# SBC_TMS9918A_ISA.net
KiCad netlist of a schematic drawn in EAGLE
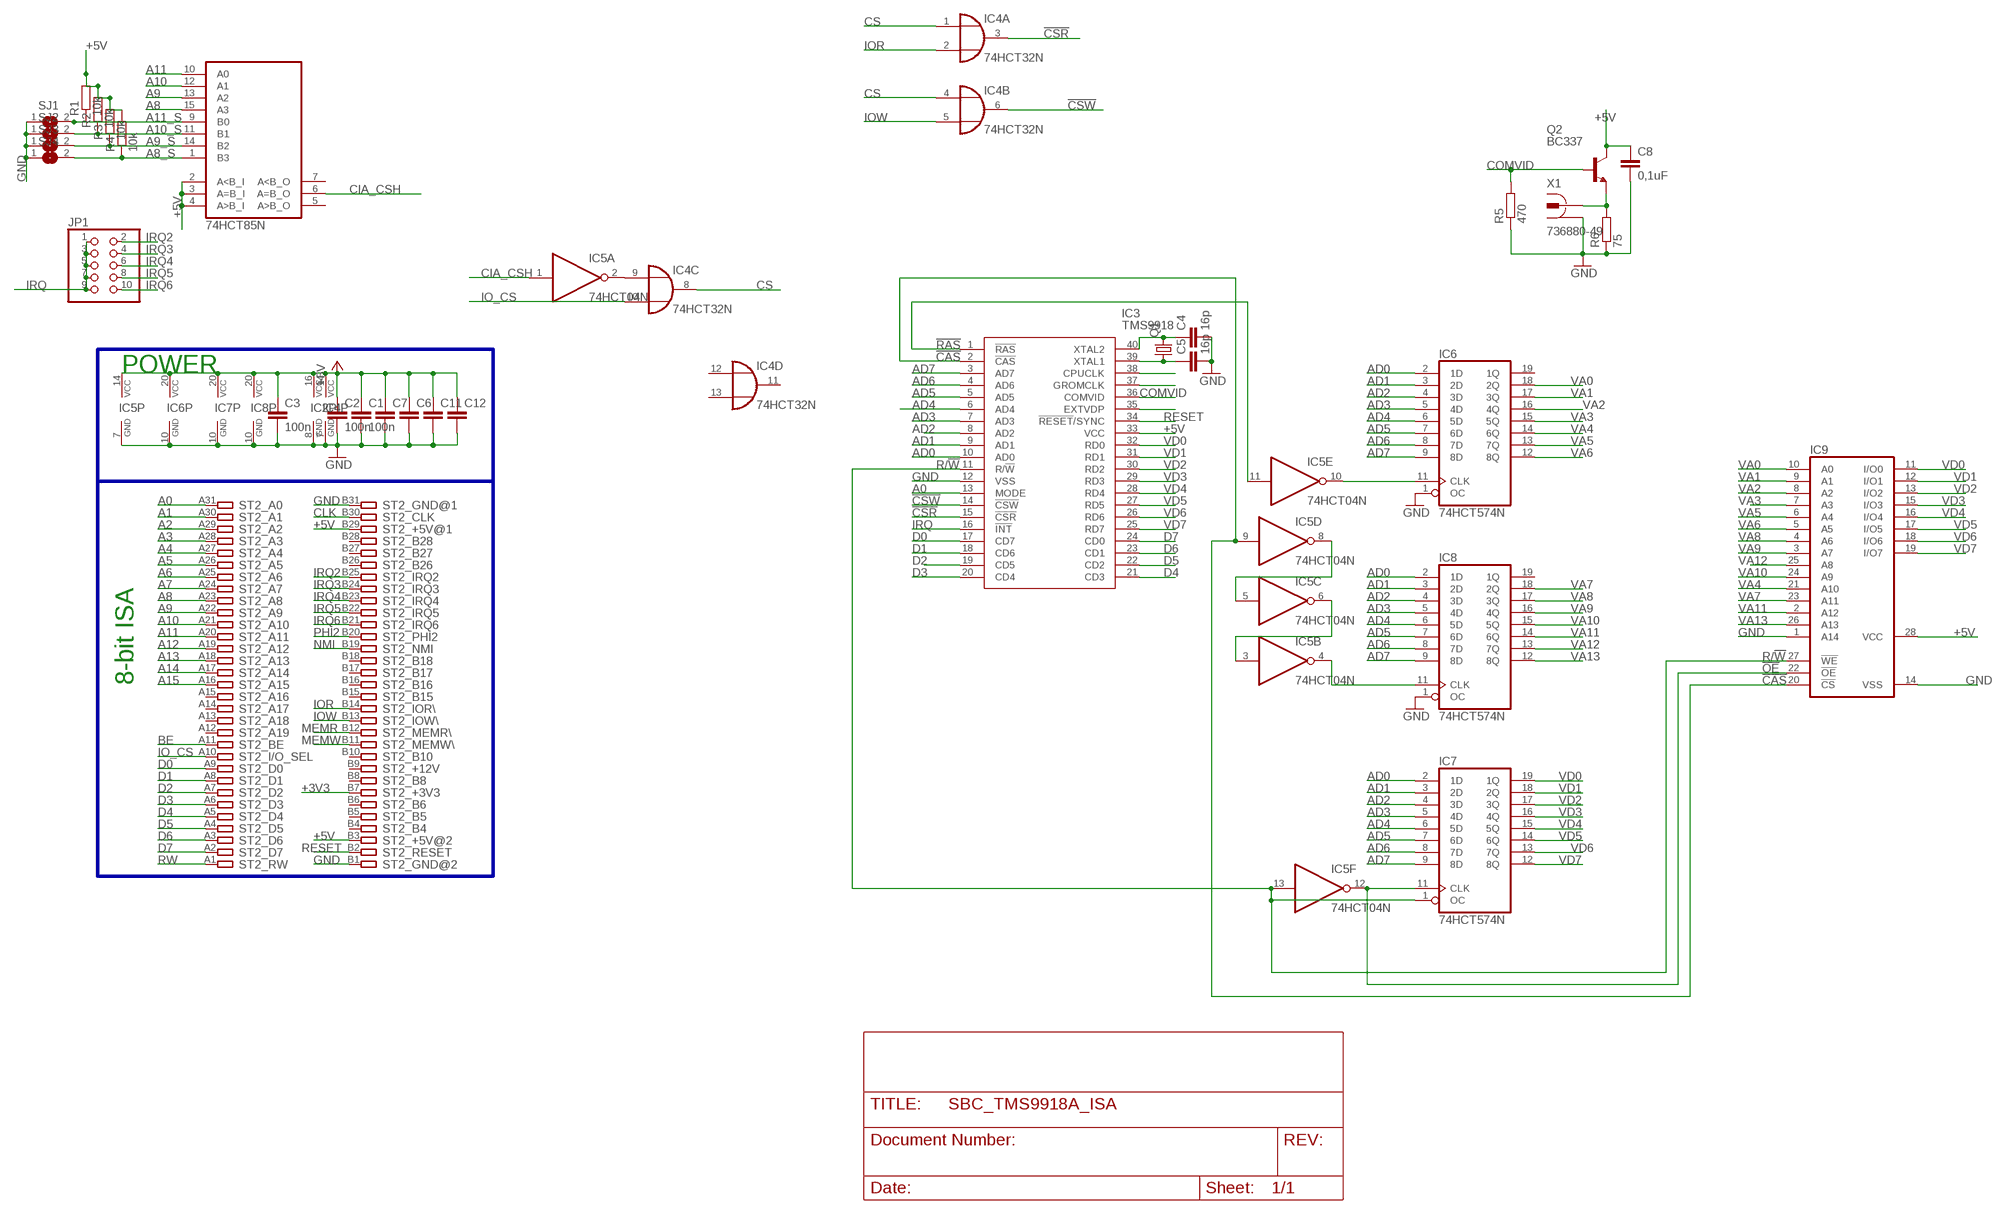
[diagram p0: schematic, sheet 1]

(export (version "E")
  (design (tool "Eeschema 10.0.6"))
  (components
    (comp (ref "C1")
      (value "100n")
      (footprint "eagle-import:C050-025X075")
      (libsource (lib "eagle-import") (part "C-EU050-025X075"))
    )
    (comp (ref "C2")
      (value "100n")
      (footprint "eagle-import:C050-025X075")
      (libsource (lib "eagle-import") (part "C-EU050-025X075"))
    )
    (comp (ref "C3")
      (value "100n")
      (footprint "eagle-import:C050-025X075")
      (libsource (lib "eagle-import") (part "C-EU050-025X075"))
    )
    (comp (ref "C4")
      (value "16p")
      (footprint "eagle-import:C050-024X044")
      (libsource (lib "eagle-import") (part "rcl_334_C-EU050-024X044"))
    )
    (comp (ref "C5")
      (value "16p")
      (footprint "eagle-import:C050-024X044")
      (libsource (lib "eagle-import") (part "rcl_334_C-EU050-024X044"))
    )
    (comp (ref "C6")
      (value "C-EU050-035X075")
      (footprint "eagle-import:C050-035X075")
      (libsource (lib "eagle-import") (part "rcl_334_C-EU050-035X075"))
    )
    (comp (ref "C7")
      (value "C-EU050-035X075")
      (footprint "eagle-import:C050-035X075")
      (libsource (lib "eagle-import") (part "rcl_334_C-EU050-035X075"))
    )
    (comp (ref "C8")
      (value "0,1uF")
      (footprint "eagle-import:C050-024X044")
      (libsource (lib "eagle-import") (part "rcl_334_C-EU050-024X044"))
    )
    (comp (ref "C11")
      (value "C-EU050-035X075")
      (footprint "eagle-import:C050-035X075")
      (libsource (lib "eagle-import") (part "rcl_334_C-EU050-035X075"))
    )
    (comp (ref "C12")
      (value "C-EU050-035X075")
      (footprint "eagle-import:C050-035X075")
      (libsource (lib "eagle-import") (part "rcl_334_C-EU050-035X075"))
    )
    (comp (ref "IC2")
      (value "74HCT85N")
      (footprint "eagle-import:DIL16")
      (libsource (lib "eagle-import") (part "7485NHCT"))
    )
    (comp (ref "IC3")
      (value "TMS9918")
      (footprint "eagle-import:DIP1524W53P254L5310H508Q40N")
      (libsource (lib "eagle-import") (part "TMS9918"))
    )
    (comp (ref "IC4")
      (value "74HCT32N")
      (footprint "eagle-import:DIL14")
      (libsource (lib "eagle-import") (part "7432NHCT"))
    )
    (comp (ref "IC5")
      (value "74HCT04N")
      (footprint "eagle-import:DIL14")
      (libsource (lib "eagle-import") (part "7404NHCT"))
    )
    (comp (ref "IC6")
      (value "74HCT574N")
      (footprint "eagle-import:DIL20")
      (libsource (lib "eagle-import") (part "74574NHCT"))
    )
    (comp (ref "IC7")
      (value "74HCT574N")
      (footprint "eagle-import:DIL20")
      (libsource (lib "eagle-import") (part "74574NHCT"))
    )
    (comp (ref "IC8")
      (value "74HCT574N")
      (footprint "eagle-import:DIL20")
      (libsource (lib "eagle-import") (part "74574NHCT"))
    )
    (comp (ref "IC9")
      (value "62256P")
      (footprint "eagle-import:DIL28-6")
      (libsource (lib "eagle-import") (part "62256P"))
    )
    (comp (ref "JP1")
      (value "PINHD-2X5")
      (footprint "eagle-import:2X05")
      (libsource (lib "eagle-import") (part "PINHD-2X5"))
    )
    (comp (ref "Q1")
      (value "CRYSTALHC49S")
      (footprint "eagle-import:HC49_S")
      (libsource (lib "eagle-import") (part "CRYSTALHC49S"))
    )
    (comp (ref "Q2")
      (value "BC337")
      (footprint "eagle-import:TO92")
      (libsource (lib "eagle-import") (part "BC337"))
    )
    (comp (ref "R1")
      (value "10k")
      (footprint "eagle-import:0207_7")
      (libsource (lib "eagle-import") (part "R-EU_0207/7"))
    )
    (comp (ref "R2")
      (value "10k")
      (footprint "eagle-import:0207_7")
      (libsource (lib "eagle-import") (part "R-EU_0207/7"))
    )
    (comp (ref "R3")
      (value "10k")
      (footprint "eagle-import:0207_7")
      (libsource (lib "eagle-import") (part "R-EU_0207/7"))
    )
    (comp (ref "R4")
      (value "10k")
      (footprint "eagle-import:0207_7")
      (libsource (lib "eagle-import") (part "R-EU_0207/7"))
    )
    (comp (ref "R5")
      (value "470")
      (footprint "eagle-import:0207_7")
      (libsource (lib "eagle-import") (part "R-EU_0207/7"))
    )
    (comp (ref "R6")
      (value "75")
      (footprint "eagle-import:0207_7")
      (libsource (lib "eagle-import") (part "R-EU_0207/7"))
    )
    (comp (ref "SJ1") (value "SJ") (footprint "eagle-import:SJ") (libsource (lib "eagle-import") (part "SJ")))
    (comp (ref "SJ2") (value "SJ") (footprint "eagle-import:SJ") (libsource (lib "eagle-import") (part "SJ")))
    (comp (ref "SJ3") (value "SJ") (footprint "eagle-import:SJ") (libsource (lib "eagle-import") (part "SJ")))
    (comp (ref "SJ4") (value "SJ") (footprint "eagle-import:SJ") (libsource (lib "eagle-import") (part "SJ")))
    (comp (ref "ST2")
      (value "IBM8BIT_ISASHORT")
      (footprint "eagle-import:APP_2X32_SHORT")
      (libsource (lib "eagle-import") (part "IBM8BIT_ISASHORT"))
    )
    (comp (ref "X1")
      (value "736880-49")
      (footprint "eagle-import:736880-49")
      (libsource (lib "eagle-import") (part "736880-49"))
    )
  )
  (nets
    (net (code "1") (name "+5V") (class "Default")
      (node (ref "C1") (pin "1") (pinfunction "1_1") (pintype "passive"))
      (node (ref "C11") (pin "1") (pinfunction "1_1") (pintype "passive"))
      (node (ref "C12") (pin "1") (pinfunction "1_1") (pintype "passive"))
      (node (ref "C2") (pin "1") (pinfunction "1_1") (pintype "passive"))
      (node (ref "C3") (pin "1") (pinfunction "1_1") (pintype "passive"))
      (node (ref "C6") (pin "1") (pinfunction "1_1") (pintype "passive"))
      (node (ref "C7") (pin "1") (pinfunction "1_1") (pintype "passive"))
      (node (ref "C8") (pin "1") (pinfunction "1_1") (pintype "passive"))
      (node (ref "IC2") (pin "16") (pinfunction "VCC_16") (pintype "power_in"))
      (node (ref "IC2") (pin "2") (pinfunction "A<B_I_2") (pintype "input"))
      (node (ref "IC2") (pin "3") (pinfunction "A=B_I_3") (pintype "input"))
      (node (ref "IC2") (pin "4") (pinfunction "A>B_I_4") (pintype "input"))
      (node (ref "IC3") (pin "33") (pinfunction "VCC_33") (pintype "bidirectional"))
      (node (ref "IC4") (pin "14") (pinfunction "VCC_14") (pintype "power_in"))
      (node (ref "IC5") (pin "14") (pinfunction "VCC_14") (pintype "power_in"))
      (node (ref "IC6") (pin "20") (pinfunction "VCC_20") (pintype "power_in"))
      (node (ref "IC7") (pin "20") (pinfunction "VCC_20") (pintype "power_in"))
      (node (ref "IC8") (pin "20") (pinfunction "VCC_20") (pintype "power_in"))
      (node (ref "IC9") (pin "28") (pinfunction "VCC_28") (pintype "power_in"))
      (node (ref "Q2") (pin "3") (pinfunction "C_3") (pintype "passive"))
      (node (ref "R1") (pin "2") (pinfunction "2_2") (pintype "passive"))
      (node (ref "R2") (pin "2") (pinfunction "2_2") (pintype "passive"))
      (node (ref "R3") (pin "2") (pinfunction "2_2") (pintype "passive"))
      (node (ref "R4") (pin "2") (pinfunction "2_2") (pintype "passive"))
      (node (ref "ST2") (pin "B29") (pinfunction "P_B29") (pintype "bidirectional"))
      (node (ref "ST2") (pin "B3") (pinfunction "P_B3") (pintype "bidirectional"))
    )
    (net (code "2") (name "/+3V3") (class "Default")
      (node (ref "ST2") (pin "B7") (pinfunction "P_B7") (pintype "bidirectional"))
    )
    (net (code "3") (name "/A0") (class "Default")
      (node (ref "IC3") (pin "13") (pinfunction "MODE_13") (pintype "bidirectional"))
      (node (ref "ST2") (pin "A31") (pinfunction "P_A31") (pintype "bidirectional"))
    )
    (net (code "4") (name "/A1") (class "Default")
      (node (ref "ST2") (pin "A30") (pinfunction "P_A30") (pintype "bidirectional"))
    )
    (net (code "5") (name "/A2") (class "Default")
      (node (ref "ST2") (pin "A29") (pinfunction "P_A29") (pintype "bidirectional"))
    )
    (net (code "6") (name "/A3") (class "Default")
      (node (ref "ST2") (pin "A28") (pinfunction "P_A28") (pintype "bidirectional"))
    )
    (net (code "7") (name "/A4") (class "Default")
      (node (ref "ST2") (pin "A27") (pinfunction "P_A27") (pintype "bidirectional"))
    )
    (net (code "8") (name "/A5") (class "Default")
      (node (ref "ST2") (pin "A26") (pinfunction "P_A26") (pintype "bidirectional"))
    )
    (net (code "9") (name "/A6") (class "Default")
      (node (ref "ST2") (pin "A25") (pinfunction "P_A25") (pintype "bidirectional"))
    )
    (net (code "10") (name "/A7") (class "Default")
      (node (ref "ST2") (pin "A24") (pinfunction "P_A24") (pintype "bidirectional"))
    )
    (net (code "11") (name "/A8") (class "Default")
      (node (ref "IC2") (pin "15") (pinfunction "A3_15") (pintype "input"))
      (node (ref "ST2") (pin "A23") (pinfunction "P_A23") (pintype "bidirectional"))
    )
    (net (code "12") (name "/A8_S") (class "Default")
      (node (ref "IC2") (pin "1") (pinfunction "B3_1") (pintype "input"))
      (node (ref "R4") (pin "1") (pinfunction "1_1") (pintype "passive"))
      (node (ref "SJ4") (pin "2") (pinfunction "2_2") (pintype "passive"))
    )
    (net (code "13") (name "/A9") (class "Default")
      (node (ref "IC2") (pin "13") (pinfunction "A2_13") (pintype "input"))
      (node (ref "ST2") (pin "A22") (pinfunction "P_A22") (pintype "bidirectional"))
    )
    (net (code "14") (name "/A9_S") (class "Default")
      (node (ref "IC2") (pin "14") (pinfunction "B2_14") (pintype "input"))
      (node (ref "R3") (pin "1") (pinfunction "1_1") (pintype "passive"))
      (node (ref "SJ3") (pin "2") (pinfunction "2_2") (pintype "passive"))
    )
    (net (code "15") (name "/A10") (class "Default")
      (node (ref "IC2") (pin "12") (pinfunction "A1_12") (pintype "input"))
      (node (ref "ST2") (pin "A21") (pinfunction "P_A21") (pintype "bidirectional"))
    )
    (net (code "16") (name "/A10_S") (class "Default")
      (node (ref "IC2") (pin "11") (pinfunction "B1_11") (pintype "input"))
      (node (ref "R2") (pin "1") (pinfunction "1_1") (pintype "passive"))
      (node (ref "SJ2") (pin "2") (pinfunction "2_2") (pintype "passive"))
    )
    (net (code "17") (name "/A11") (class "Default")
      (node (ref "IC2") (pin "10") (pinfunction "A0_10") (pintype "input"))
      (node (ref "ST2") (pin "A20") (pinfunction "P_A20") (pintype "bidirectional"))
    )
    (net (code "18") (name "/A11_S") (class "Default")
      (node (ref "IC2") (pin "9") (pinfunction "B0_9") (pintype "input"))
      (node (ref "R1") (pin "1") (pinfunction "1_1") (pintype "passive"))
      (node (ref "SJ1") (pin "2") (pinfunction "2_2") (pintype "passive"))
    )
    (net (code "19") (name "/A12") (class "Default")
      (node (ref "ST2") (pin "A19") (pinfunction "P_A19") (pintype "bidirectional"))
    )
    (net (code "20") (name "/A13") (class "Default")
      (node (ref "ST2") (pin "A18") (pinfunction "P_A18") (pintype "bidirectional"))
    )
    (net (code "21") (name "/A14") (class "Default")
      (node (ref "ST2") (pin "A17") (pinfunction "P_A17") (pintype "bidirectional"))
    )
    (net (code "22") (name "/A15") (class "Default")
      (node (ref "ST2") (pin "A16") (pinfunction "P_A16") (pintype "bidirectional"))
    )
    (net (code "23") (name "/AD0") (class "Default")
      (node (ref "IC3") (pin "10") (pinfunction "AD0_10") (pintype "bidirectional"))
      (node (ref "IC6") (pin "2") (pinfunction "1D_2") (pintype "input"))
      (node (ref "IC7") (pin "2") (pinfunction "1D_2") (pintype "input"))
      (node (ref "IC8") (pin "2") (pinfunction "1D_2") (pintype "input"))
    )
    (net (code "24") (name "/AD1") (class "Default")
      (node (ref "IC3") (pin "9") (pinfunction "AD1_9") (pintype "bidirectional"))
      (node (ref "IC6") (pin "3") (pinfunction "2D_3") (pintype "input"))
      (node (ref "IC7") (pin "3") (pinfunction "2D_3") (pintype "input"))
      (node (ref "IC8") (pin "3") (pinfunction "2D_3") (pintype "input"))
    )
    (net (code "25") (name "/AD2") (class "Default")
      (node (ref "IC3") (pin "8") (pinfunction "AD2_8") (pintype "bidirectional"))
      (node (ref "IC6") (pin "4") (pinfunction "3D_4") (pintype "input"))
      (node (ref "IC7") (pin "4") (pinfunction "3D_4") (pintype "input"))
      (node (ref "IC8") (pin "4") (pinfunction "3D_4") (pintype "input"))
    )
    (net (code "26") (name "/AD3") (class "Default")
      (node (ref "IC3") (pin "7") (pinfunction "AD3_7") (pintype "bidirectional"))
      (node (ref "IC6") (pin "5") (pinfunction "4D_5") (pintype "input"))
      (node (ref "IC7") (pin "5") (pinfunction "4D_5") (pintype "input"))
      (node (ref "IC8") (pin "5") (pinfunction "4D_5") (pintype "input"))
    )
    (net (code "27") (name "/AD4") (class "Default")
      (node (ref "IC3") (pin "6") (pinfunction "AD4_6") (pintype "bidirectional"))
      (node (ref "IC6") (pin "6") (pinfunction "5D_6") (pintype "input"))
      (node (ref "IC7") (pin "6") (pinfunction "5D_6") (pintype "input"))
      (node (ref "IC8") (pin "6") (pinfunction "5D_6") (pintype "input"))
    )
    (net (code "28") (name "/AD5") (class "Default")
      (node (ref "IC3") (pin "5") (pinfunction "AD5_5") (pintype "bidirectional"))
      (node (ref "IC6") (pin "7") (pinfunction "6D_7") (pintype "input"))
      (node (ref "IC7") (pin "7") (pinfunction "6D_7") (pintype "input"))
      (node (ref "IC8") (pin "7") (pinfunction "6D_7") (pintype "input"))
    )
    (net (code "29") (name "/AD6") (class "Default")
      (node (ref "IC3") (pin "4") (pinfunction "AD6_4") (pintype "bidirectional"))
      (node (ref "IC6") (pin "8") (pinfunction "7D_8") (pintype "input"))
      (node (ref "IC7") (pin "8") (pinfunction "7D_8") (pintype "input"))
      (node (ref "IC8") (pin "8") (pinfunction "7D_8") (pintype "input"))
    )
    (net (code "30") (name "/AD7") (class "Default")
      (node (ref "IC3") (pin "3") (pinfunction "AD7_3") (pintype "bidirectional"))
      (node (ref "IC6") (pin "9") (pinfunction "8D_9") (pintype "input"))
      (node (ref "IC7") (pin "9") (pinfunction "8D_9") (pintype "input"))
      (node (ref "IC8") (pin "9") (pinfunction "8D_9") (pintype "input"))
    )
    (net (code "31") (name "/BE") (class "Default")
      (node (ref "ST2") (pin "A11") (pinfunction "P_A11") (pintype "bidirectional"))
    )
    (net (code "32") (name "/CIA_CSH") (class "Default")
      (node (ref "IC2") (pin "6") (pinfunction "A=B_O_6") (pintype "output"))
      (node (ref "IC5") (pin "1") (pinfunction "I_1") (pintype "input"))
    )
    (net (code "33") (name "/CLK") (class "Default")
      (node (ref "ST2") (pin "B30") (pinfunction "P_B30") (pintype "bidirectional"))
    )
    (net (code "34") (name "/COMVID") (class "Default")
      (node (ref "IC3") (pin "36") (pinfunction "COMVID_36") (pintype "bidirectional"))
      (node (ref "Q2") (pin "2") (pinfunction "B_2") (pintype "passive"))
      (node (ref "R5") (pin "2") (pinfunction "2_2") (pintype "passive"))
    )
    (net (code "35") (name "/CS") (class "Default")
      (node (ref "IC4") (pin "1") (pinfunction "I0_1") (pintype "input"))
      (node (ref "IC4") (pin "4") (pinfunction "I0_4") (pintype "input"))
      (node (ref "IC4") (pin "8") (pinfunction "O_8") (pintype "output"))
    )
    (net (code "36") (name "/D0") (class "Default")
      (node (ref "IC3") (pin "17") (pinfunction "CD7_17") (pintype "bidirectional"))
      (node (ref "ST2") (pin "A9") (pinfunction "P_A9") (pintype "bidirectional"))
    )
    (net (code "37") (name "/D1") (class "Default")
      (node (ref "IC3") (pin "18") (pinfunction "CD6_18") (pintype "bidirectional"))
      (node (ref "ST2") (pin "A8") (pinfunction "P_A8") (pintype "bidirectional"))
    )
    (net (code "38") (name "/D2") (class "Default")
      (node (ref "IC3") (pin "19") (pinfunction "CD5_19") (pintype "bidirectional"))
      (node (ref "ST2") (pin "A7") (pinfunction "P_A7") (pintype "bidirectional"))
    )
    (net (code "39") (name "/D3") (class "Default")
      (node (ref "IC3") (pin "20") (pinfunction "CD4_20") (pintype "bidirectional"))
      (node (ref "ST2") (pin "A6") (pinfunction "P_A6") (pintype "bidirectional"))
    )
    (net (code "40") (name "/D4") (class "Default")
      (node (ref "IC3") (pin "21") (pinfunction "CD3_21") (pintype "bidirectional"))
      (node (ref "ST2") (pin "A5") (pinfunction "P_A5") (pintype "bidirectional"))
    )
    (net (code "41") (name "/D5") (class "Default")
      (node (ref "IC3") (pin "22") (pinfunction "CD2_22") (pintype "bidirectional"))
      (node (ref "ST2") (pin "A4") (pinfunction "P_A4") (pintype "bidirectional"))
    )
    (net (code "42") (name "/D6") (class "Default")
      (node (ref "IC3") (pin "23") (pinfunction "CD1_23") (pintype "bidirectional"))
      (node (ref "ST2") (pin "A3") (pinfunction "P_A3") (pintype "bidirectional"))
    )
    (net (code "43") (name "/D7") (class "Default")
      (node (ref "IC3") (pin "24") (pinfunction "CD0_24") (pintype "bidirectional"))
      (node (ref "ST2") (pin "A2") (pinfunction "P_A2") (pintype "bidirectional"))
    )
    (net (code "44") (name "/IOR") (class "Default")
      (node (ref "IC4") (pin "2") (pinfunction "I1_2") (pintype "input"))
      (node (ref "ST2") (pin "B14") (pinfunction "P_B14") (pintype "bidirectional"))
    )
    (net (code "45") (name "/IOW") (class "Default")
      (node (ref "IC4") (pin "5") (pinfunction "I1_5") (pintype "input"))
      (node (ref "ST2") (pin "B13") (pinfunction "P_B13") (pintype "bidirectional"))
    )
    (net (code "46") (name "/IO_CS") (class "Default")
      (node (ref "IC4") (pin "10") (pinfunction "I1_10") (pintype "input"))
      (node (ref "ST2") (pin "A10") (pinfunction "P_A10") (pintype "bidirectional"))
    )
    (net (code "47") (name "/IRQ") (class "Default")
      (node (ref "IC3") (pin "16") (pinfunction "~{INT}_16") (pintype "bidirectional"))
      (node (ref "JP1") (pin "1") (pinfunction "1_1") (pintype "passive"))
      (node (ref "JP1") (pin "3") (pinfunction "3_3") (pintype "passive"))
      (node (ref "JP1") (pin "5") (pinfunction "5_5") (pintype "passive"))
      (node (ref "JP1") (pin "7") (pinfunction "7_7") (pintype "passive"))
      (node (ref "JP1") (pin "9") (pinfunction "9_9") (pintype "passive"))
    )
    (net (code "48") (name "/IRQ2") (class "Default")
      (node (ref "JP1") (pin "2") (pinfunction "2_2") (pintype "passive"))
      (node (ref "ST2") (pin "B25") (pinfunction "P_B25") (pintype "bidirectional"))
    )
    (net (code "49") (name "/IRQ3") (class "Default")
      (node (ref "JP1") (pin "4") (pinfunction "4_4") (pintype "passive"))
      (node (ref "ST2") (pin "B24") (pinfunction "P_B24") (pintype "bidirectional"))
    )
    (net (code "50") (name "/IRQ4") (class "Default")
      (node (ref "JP1") (pin "6") (pinfunction "6_6") (pintype "passive"))
      (node (ref "ST2") (pin "B23") (pinfunction "P_B23") (pintype "bidirectional"))
    )
    (net (code "51") (name "/IRQ5") (class "Default")
      (node (ref "JP1") (pin "8") (pinfunction "8_8") (pintype "passive"))
      (node (ref "ST2") (pin "B22") (pinfunction "P_B22") (pintype "bidirectional"))
    )
    (net (code "52") (name "/IRQ6") (class "Default")
      (node (ref "JP1") (pin "10") (pinfunction "10_10") (pintype "passive"))
      (node (ref "ST2") (pin "B21") (pinfunction "P_B21") (pintype "bidirectional"))
    )
    (net (code "53") (name "/MEMR") (class "Default")
      (node (ref "ST2") (pin "B12") (pinfunction "P_B12") (pintype "bidirectional"))
    )
    (net (code "54") (name "/MEMW") (class "Default")
      (node (ref "ST2") (pin "B11") (pinfunction "P_B11") (pintype "bidirectional"))
    )
    (net (code "55") (name "/NMI") (class "Default")
      (node (ref "ST2") (pin "B19") (pinfunction "P_B19") (pintype "bidirectional"))
    )
    (net (code "56") (name "/PHI2") (class "Default")
      (node (ref "ST2") (pin "B20") (pinfunction "P_B20") (pintype "bidirectional"))
    )
    (net (code "57") (name "/RESET") (class "Default")
      (node (ref "IC3") (pin "34") (pinfunction "~{RESET}/SYNC_34") (pintype "bidirectional"))
      (node (ref "ST2") (pin "B2") (pinfunction "P_B2") (pintype "bidirectional"))
    )
    (net (code "58") (name "/RW") (class "Default")
      (node (ref "ST2") (pin "A1") (pinfunction "P_A1") (pintype "bidirectional"))
    )
    (net (code "59") (name "/R{slash}~{W}") (class "Default")
      (node (ref "IC3") (pin "11") (pinfunction "R/~{W}_11") (pintype "bidirectional"))
      (node (ref "IC5") (pin "13") (pinfunction "I_13") (pintype "input"))
      (node (ref "IC7") (pin "1") (pinfunction "OC_1") (pintype "input"))
      (node (ref "IC9") (pin "27") (pinfunction "~{WE}_27") (pintype "input"))
    )
    (net (code "60") (name "/VA0") (class "Default")
      (node (ref "IC6") (pin "18") (pinfunction "2Q_18") (pintype "tri_state"))
      (node (ref "IC9") (pin "10") (pinfunction "A0_10") (pintype "input"))
    )
    (net (code "61") (name "/VA1") (class "Default")
      (node (ref "IC6") (pin "17") (pinfunction "3Q_17") (pintype "tri_state"))
      (node (ref "IC9") (pin "9") (pinfunction "A1_9") (pintype "input"))
    )
    (net (code "62") (name "/VA2") (class "Default")
      (node (ref "IC6") (pin "16") (pinfunction "4Q_16") (pintype "tri_state"))
      (node (ref "IC9") (pin "8") (pinfunction "A2_8") (pintype "input"))
    )
    (net (code "63") (name "/VA3") (class "Default")
      (node (ref "IC6") (pin "15") (pinfunction "5Q_15") (pintype "tri_state"))
      (node (ref "IC9") (pin "7") (pinfunction "A3_7") (pintype "input"))
    )
    (net (code "64") (name "/VA4") (class "Default")
      (node (ref "IC6") (pin "14") (pinfunction "6Q_14") (pintype "tri_state"))
      (node (ref "IC9") (pin "21") (pinfunction "A10_21") (pintype "input"))
    )
    (net (code "65") (name "/VA5") (class "Default")
      (node (ref "IC6") (pin "13") (pinfunction "7Q_13") (pintype "tri_state"))
      (node (ref "IC9") (pin "6") (pinfunction "A4_6") (pintype "input"))
    )
    (net (code "66") (name "/VA6") (class "Default")
      (node (ref "IC6") (pin "12") (pinfunction "8Q_12") (pintype "tri_state"))
      (node (ref "IC9") (pin "5") (pinfunction "A5_5") (pintype "input"))
    )
    (net (code "67") (name "/VA7") (class "Default")
      (node (ref "IC8") (pin "18") (pinfunction "2Q_18") (pintype "tri_state"))
      (node (ref "IC9") (pin "23") (pinfunction "A11_23") (pintype "input"))
    )
    (net (code "68") (name "/VA8") (class "Default")
      (node (ref "IC8") (pin "17") (pinfunction "3Q_17") (pintype "tri_state"))
      (node (ref "IC9") (pin "4") (pinfunction "A6_4") (pintype "input"))
    )
    (net (code "69") (name "/VA9") (class "Default")
      (node (ref "IC8") (pin "16") (pinfunction "4Q_16") (pintype "tri_state"))
      (node (ref "IC9") (pin "3") (pinfunction "A7_3") (pintype "input"))
    )
    (net (code "70") (name "/VA10") (class "Default")
      (node (ref "IC8") (pin "15") (pinfunction "5Q_15") (pintype "tri_state"))
      (node (ref "IC9") (pin "24") (pinfunction "A9_24") (pintype "input"))
    )
    (net (code "71") (name "/VA11") (class "Default")
      (node (ref "IC8") (pin "14") (pinfunction "6Q_14") (pintype "tri_state"))
      (node (ref "IC9") (pin "2") (pinfunction "A12_2") (pintype "input"))
    )
    (net (code "72") (name "/VA12") (class "Default")
      (node (ref "IC8") (pin "13") (pinfunction "7Q_13") (pintype "tri_state"))
      (node (ref "IC9") (pin "25") (pinfunction "A8_25") (pintype "input"))
    )
    (net (code "73") (name "/VA13") (class "Default")
      (node (ref "IC8") (pin "12") (pinfunction "8Q_12") (pintype "tri_state"))
      (node (ref "IC9") (pin "26") (pinfunction "A13_26") (pintype "input"))
    )
    (net (code "74") (name "/VD0") (class "Default")
      (node (ref "IC3") (pin "32") (pinfunction "RD0_32") (pintype "bidirectional"))
      (node (ref "IC7") (pin "19") (pinfunction "1Q_19") (pintype "tri_state"))
      (node (ref "IC9") (pin "11") (pinfunction "I/O0_11") (pintype "bidirectional"))
    )
    (net (code "75") (name "/VD1") (class "Default")
      (node (ref "IC3") (pin "31") (pinfunction "RD1_31") (pintype "bidirectional"))
      (node (ref "IC7") (pin "18") (pinfunction "2Q_18") (pintype "tri_state"))
      (node (ref "IC9") (pin "12") (pinfunction "I/O1_12") (pintype "bidirectional"))
    )
    (net (code "76") (name "/VD2") (class "Default")
      (node (ref "IC3") (pin "30") (pinfunction "RD2_30") (pintype "bidirectional"))
      (node (ref "IC7") (pin "17") (pinfunction "3Q_17") (pintype "tri_state"))
      (node (ref "IC9") (pin "13") (pinfunction "I/O2_13") (pintype "bidirectional"))
    )
    (net (code "77") (name "/VD3") (class "Default")
      (node (ref "IC3") (pin "29") (pinfunction "RD3_29") (pintype "bidirectional"))
      (node (ref "IC7") (pin "16") (pinfunction "4Q_16") (pintype "tri_state"))
      (node (ref "IC9") (pin "15") (pinfunction "I/O3_15") (pintype "bidirectional"))
    )
    (net (code "78") (name "/VD4") (class "Default")
      (node (ref "IC3") (pin "28") (pinfunction "RD4_28") (pintype "bidirectional"))
      (node (ref "IC7") (pin "15") (pinfunction "5Q_15") (pintype "tri_state"))
      (node (ref "IC9") (pin "16") (pinfunction "I/O4_16") (pintype "bidirectional"))
    )
    (net (code "79") (name "/VD5") (class "Default")
      (node (ref "IC3") (pin "27") (pinfunction "RD5_27") (pintype "bidirectional"))
      (node (ref "IC7") (pin "14") (pinfunction "6Q_14") (pintype "tri_state"))
      (node (ref "IC9") (pin "17") (pinfunction "I/O5_17") (pintype "bidirectional"))
    )
    (net (code "80") (name "/VD6") (class "Default")
      (node (ref "IC3") (pin "26") (pinfunction "RD6_26") (pintype "bidirectional"))
      (node (ref "IC7") (pin "13") (pinfunction "7Q_13") (pintype "tri_state"))
      (node (ref "IC9") (pin "18") (pinfunction "I/O6_18") (pintype "bidirectional"))
    )
    (net (code "81") (name "/VD7") (class "Default")
      (node (ref "IC3") (pin "25") (pinfunction "RD7_25") (pintype "bidirectional"))
      (node (ref "IC7") (pin "12") (pinfunction "8Q_12") (pintype "tri_state"))
      (node (ref "IC9") (pin "19") (pinfunction "I/O7_19") (pintype "bidirectional"))
    )
    (net (code "82") (name "/~{CAS}") (class "Default")
      (node (ref "IC3") (pin "2") (pinfunction "~{CAS}_2") (pintype "bidirectional"))
      (node (ref "IC5") (pin "9") (pinfunction "I_9") (pintype "input"))
      (node (ref "IC9") (pin "20") (pinfunction "~{CS}_20") (pintype "input"))
    )
    (net (code "83") (name "/~{CSR}") (class "Default")
      (node (ref "IC3") (pin "15") (pinfunction "~{CSR}_15") (pintype "bidirectional"))
      (node (ref "IC4") (pin "3") (pinfunction "O_3") (pintype "output"))
    )
    (net (code "84") (name "/~{CSW}") (class "Default")
      (node (ref "IC3") (pin "14") (pinfunction "~{CSW}_14") (pintype "bidirectional"))
      (node (ref "IC4") (pin "6") (pinfunction "O_6") (pintype "output"))
    )
    (net (code "85") (name "/~{OE}") (class "Default")
      (node (ref "IC5") (pin "12") (pinfunction "O_12") (pintype "output"))
      (node (ref "IC7") (pin "11") (pinfunction "CLK_11") (pintype "input"))
      (node (ref "IC9") (pin "22") (pinfunction "~{OE}_22") (pintype "input"))
    )
    (net (code "86") (name "/~{RAS}") (class "Default")
      (node (ref "IC3") (pin "1") (pinfunction "~{RAS}_1") (pintype "bidirectional"))
      (node (ref "IC5") (pin "11") (pinfunction "I_11") (pintype "input"))
    )
    (net (code "87") (name "GND") (class "Default")
      (node (ref "C1") (pin "2") (pinfunction "2_2") (pintype "passive"))
      (node (ref "C11") (pin "2") (pinfunction "2_2") (pintype "passive"))
      (node (ref "C12") (pin "2") (pinfunction "2_2") (pintype "passive"))
      (node (ref "C2") (pin "2") (pinfunction "2_2") (pintype "passive"))
      (node (ref "C3") (pin "2") (pinfunction "2_2") (pintype "passive"))
      (node (ref "C4") (pin "2") (pinfunction "2_2") (pintype "passive"))
      (node (ref "C5") (pin "2") (pinfunction "2_2") (pintype "passive"))
      (node (ref "C6") (pin "2") (pinfunction "2_2") (pintype "passive"))
      (node (ref "C7") (pin "2") (pinfunction "2_2") (pintype "passive"))
      (node (ref "C8") (pin "2") (pinfunction "2_2") (pintype "passive"))
      (node (ref "IC2") (pin "8") (pinfunction "GND_8") (pintype "power_in"))
      (node (ref "IC3") (pin "12") (pinfunction "VSS_12") (pintype "bidirectional"))
      (node (ref "IC4") (pin "7") (pinfunction "GND_7") (pintype "power_in"))
      (node (ref "IC5") (pin "7") (pinfunction "GND_7") (pintype "power_in"))
      (node (ref "IC6") (pin "1") (pinfunction "OC_1") (pintype "input"))
      (node (ref "IC6") (pin "10") (pinfunction "GND_10") (pintype "power_in"))
      (node (ref "IC7") (pin "10") (pinfunction "GND_10") (pintype "power_in"))
      (node (ref "IC8") (pin "1") (pinfunction "OC_1") (pintype "input"))
      (node (ref "IC8") (pin "10") (pinfunction "GND_10") (pintype "power_in"))
      (node (ref "IC9") (pin "1") (pinfunction "A14_1") (pintype "input"))
      (node (ref "IC9") (pin "14") (pinfunction "VSS_14") (pintype "power_in"))
      (node (ref "R5") (pin "1") (pinfunction "1_1") (pintype "passive"))
      (node (ref "R6") (pin "1") (pinfunction "1_1") (pintype "passive"))
      (node (ref "SJ1") (pin "1") (pinfunction "1_1") (pintype "passive"))
      (node (ref "SJ2") (pin "1") (pinfunction "1_1") (pintype "passive"))
      (node (ref "SJ3") (pin "1") (pinfunction "1_1") (pintype "passive"))
      (node (ref "SJ4") (pin "1") (pinfunction "1_1") (pintype "passive"))
      (node (ref "ST2") (pin "B1") (pinfunction "P_B1") (pintype "bidirectional"))
      (node (ref "ST2") (pin "B31") (pinfunction "P_B31") (pintype "bidirectional"))
      (node (ref "X1") (pin "1") (pinfunction "1_1") (pintype "passive"))
      (node (ref "X1") (pin "1@1") (pinfunction "1_1@1") (pintype "passive"))
      (node (ref "X1") (pin "1@2") (pinfunction "1_1@2") (pintype "passive"))
    )
    (net (code "88") (name "Net-(IC3-XTAL1)") (class "Default")
      (node (ref "C5") (pin "1") (pinfunction "1_1") (pintype "passive"))
      (node (ref "IC3") (pin "39") (pinfunction "XTAL1_39") (pintype "bidirectional"))
      (node (ref "Q1") (pin "1") (pinfunction "1_1") (pintype "passive"))
    )
    (net (code "89") (name "Net-(IC3-XTAL2)") (class "Default")
      (node (ref "C4") (pin "1") (pinfunction "1_1") (pintype "passive"))
      (node (ref "IC3") (pin "40") (pinfunction "XTAL2_40") (pintype "bidirectional"))
      (node (ref "Q1") (pin "2") (pinfunction "2_2") (pintype "passive"))
    )
    (net (code "90") (name "Net-(IC4C-I0)") (class "Default")
      (node (ref "IC4") (pin "9") (pinfunction "I0_9") (pintype "input"))
      (node (ref "IC5") (pin "2") (pinfunction "O_2") (pintype "output"))
    )
    (net (code "91") (name "Net-(IC5B-I)") (class "Default")
      (node (ref "IC5") (pin "3") (pinfunction "I_3") (pintype "input"))
      (node (ref "IC5") (pin "6") (pinfunction "O_6") (pintype "output"))
    )
    (net (code "92") (name "Net-(IC5B-O)") (class "Default")
      (node (ref "IC5") (pin "4") (pinfunction "O_4") (pintype "output"))
      (node (ref "IC8") (pin "11") (pinfunction "CLK_11") (pintype "input"))
    )
    (net (code "93") (name "Net-(IC5C-I)") (class "Default")
      (node (ref "IC5") (pin "5") (pinfunction "I_5") (pintype "input"))
      (node (ref "IC5") (pin "8") (pinfunction "O_8") (pintype "output"))
    )
    (net (code "94") (name "Net-(IC5E-O)") (class "Default")
      (node (ref "IC5") (pin "10") (pinfunction "O_10") (pintype "output"))
      (node (ref "IC6") (pin "11") (pinfunction "CLK_11") (pintype "input"))
    )
    (net (code "95") (name "Net-(Q2-E)") (class "Default")
      (node (ref "Q2") (pin "1") (pinfunction "E_1") (pintype "passive"))
      (node (ref "R6") (pin "2") (pinfunction "2_2") (pintype "passive"))
      (node (ref "X1") (pin "2") (pinfunction "2_2") (pintype "passive"))
    )
    (net (code "96") (name "unconnected-(IC2A-A<B_O-Pad7)") (class "Default")
      (node (ref "IC2") (pin "7") (pinfunction "A<B_O_7") (pintype "output"))
    )
    (net (code "97") (name "unconnected-(IC2A-A>B_O-Pad5)") (class "Default")
      (node (ref "IC2") (pin "5") (pinfunction "A>B_O_5") (pintype "output"))
    )
    (net (code "98") (name "unconnected-(IC3-CPUCLK-Pad38)") (class "Default")
      (node (ref "IC3") (pin "38") (pinfunction "CPUCLK_38") (pintype "bidirectional"))
    )
    (net (code "99") (name "unconnected-(IC3-EXTVDP-Pad35)") (class "Default")
      (node (ref "IC3") (pin "35") (pinfunction "EXTVDP_35") (pintype "bidirectional"))
    )
    (net (code "100") (name "unconnected-(IC3-GROMCLK-Pad37)") (class "Default")
      (node (ref "IC3") (pin "37") (pinfunction "GROMCLK_37") (pintype "bidirectional"))
    )
    (net (code "101") (name "unconnected-(IC4D-I0-Pad12)") (class "Default")
      (node (ref "IC4") (pin "12") (pinfunction "I0_12") (pintype "input"))
    )
    (net (code "102") (name "unconnected-(IC4D-I1-Pad13)") (class "Default")
      (node (ref "IC4") (pin "13") (pinfunction "I1_13") (pintype "input"))
    )
    (net (code "103") (name "unconnected-(IC4D-O-Pad11)") (class "Default")
      (node (ref "IC4") (pin "11") (pinfunction "O_11") (pintype "output"))
    )
    (net (code "104") (name "unconnected-(IC6A-1Q-Pad19)") (class "Default")
      (node (ref "IC6") (pin "19") (pinfunction "1Q_19") (pintype "tri_state"))
    )
    (net (code "105") (name "unconnected-(IC8A-1Q-Pad19)") (class "Default")
      (node (ref "IC8") (pin "19") (pinfunction "1Q_19") (pintype "tri_state"))
    )
    (net (code "106") (name "unconnected-(ST2A-P-PadB9)") (class "Default")
      (node (ref "ST2") (pin "B9") (pinfunction "P_B9") (pintype "bidirectional"))
    )
    (net (code "107") (name "unconnected-(ST2AA-P-PadB16)") (class "Default")
      (node (ref "ST2") (pin "B16") (pinfunction "P_B16") (pintype "bidirectional"))
    )
    (net (code "108") (name "unconnected-(ST2AB-P-PadB17)") (class "Default")
      (node (ref "ST2") (pin "B17") (pinfunction "P_B17") (pintype "bidirectional"))
    )
    (net (code "109") (name "unconnected-(ST2AC-P-PadB18)") (class "Default")
      (node (ref "ST2") (pin "B18") (pinfunction "P_B18") (pintype "bidirectional"))
    )
    (net (code "110") (name "unconnected-(ST2AD-P-PadB26)") (class "Default")
      (node (ref "ST2") (pin "B26") (pinfunction "P_B26") (pintype "bidirectional"))
    )
    (net (code "111") (name "unconnected-(ST2AE-P-PadB27)") (class "Default")
      (node (ref "ST2") (pin "B27") (pinfunction "P_B27") (pintype "bidirectional"))
    )
    (net (code "112") (name "unconnected-(ST2AF-P-PadB28)") (class "Default")
      (node (ref "ST2") (pin "B28") (pinfunction "P_B28") (pintype "bidirectional"))
    )
    (net (code "113") (name "unconnected-(ST2AG-P-PadB4)") (class "Default")
      (node (ref "ST2") (pin "B4") (pinfunction "P_B4") (pintype "bidirectional"))
    )
    (net (code "114") (name "unconnected-(ST2AH-P-PadB5)") (class "Default")
      (node (ref "ST2") (pin "B5") (pinfunction "P_B5") (pintype "bidirectional"))
    )
    (net (code "115") (name "unconnected-(ST2AI-P-PadB6)") (class "Default")
      (node (ref "ST2") (pin "B6") (pinfunction "P_B6") (pintype "bidirectional"))
    )
    (net (code "116") (name "unconnected-(ST2AJ-P-PadB8)") (class "Default")
      (node (ref "ST2") (pin "B8") (pinfunction "P_B8") (pintype "bidirectional"))
    )
    (net (code "117") (name "unconnected-(ST2M-P-PadA15)") (class "Default")
      (node (ref "ST2") (pin "A15") (pinfunction "P_A15") (pintype "bidirectional"))
    )
    (net (code "118") (name "unconnected-(ST2N-P-PadA14)") (class "Default")
      (node (ref "ST2") (pin "A14") (pinfunction "P_A14") (pintype "bidirectional"))
    )
    (net (code "119") (name "unconnected-(ST2O-P-PadA13)") (class "Default")
      (node (ref "ST2") (pin "A13") (pinfunction "P_A13") (pintype "bidirectional"))
    )
    (net (code "120") (name "unconnected-(ST2P-P-PadA12)") (class "Default")
      (node (ref "ST2") (pin "A12") (pinfunction "P_A12") (pintype "bidirectional"))
    )
    (net (code "121") (name "unconnected-(ST2Y-P-PadB10)") (class "Default")
      (node (ref "ST2") (pin "B10") (pinfunction "P_B10") (pintype "bidirectional"))
    )
    (net (code "122") (name "unconnected-(ST2Z-P-PadB15)") (class "Default")
      (node (ref "ST2") (pin "B15") (pinfunction "P_B15") (pintype "bidirectional"))
    )
  )
)
